# Motor_Phase.net
KiCad netlist of a schematic drawn in Altium Designer
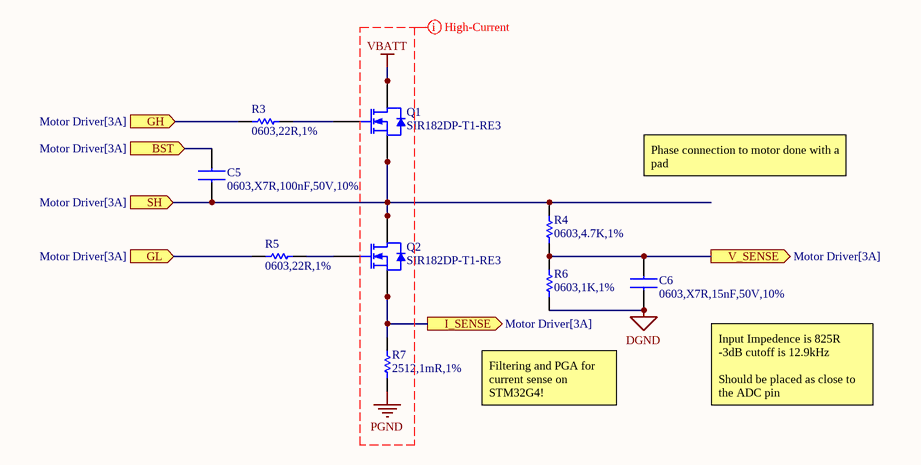
[diagram p0: Motor Phase.SchDoc]

(export (version "E")
  (design (tool "Eeschema 10.0.6"))
  (components
    (comp (ref "C5")
      (value "0603,X7R,100nF,50V,10%")
      (footprint "CAPC1608X90N")
      (description "50V 100nF X7R ±10% 0603 Multilayer Ceramic Capacitors MLCC - SMD/SMT ROHS")
      (fields
        (field (name "MANUFACTURER_PART_NUMBER") "CC0603KRX7R9BB104")
        (field (name "MOUSER PART NUMBER") "603-CC603KRX7R9BB104")
      )
      (libsource (lib "ESC") (part "CC0603KRX7R9BB104"))
    )
    (comp (ref "C6")
      (value "0603,X7R,15nF,50V,10%")
      (footprint "CAPC1608X90N")
      (description "50V 15nF X7R ±10% 0603 Multilayer Ceramic Capacitors MLCC - SMD/SMT ROHS")
      (fields
        (field (name "MANUFACTURER_PART_NUMBER") "CC0603KRX7R9BB153")
        (field (name "MOUSER PART NUMBER") "603-CC603KRX7R9BB104")
      )
      (libsource (lib "ESC") (part "CC0603KRX7R9BB153"))
    )
    (comp (ref "Q1")
      (value "SIR182DP-T1-RE3")
      (footprint "POWERPAK-SO-8_L5.9-W4.9-P1.27-LS6.2-BL")
      (description "60V 117A 2.8mΩ@10V,15A 2V 1 N-Channel PowerPAKSO-8 MOSFETs ROHS")
      (fields (field (name "LCSC PART #") "C467943"))
      (libsource (lib "ESC") (part "SIR182DP-T1-RE3"))
    )
    (comp (ref "Q2")
      (value "SIR182DP-T1-RE3")
      (footprint "POWERPAK-SO-8_L5.9-W4.9-P1.27-LS6.2-BL")
      (description "60V 117A 2.8mΩ@10V,15A 2V 1 N-Channel PowerPAKSO-8 MOSFETs ROHS")
      (fields (field (name "LCSC PART #") "C467943"))
      (libsource (lib "ESC") (part "SIR182DP-T1-RE3"))
    )
    (comp (ref "R3")
      (value "0603,22R,1%")
      (footprint "RESC1608X55N")
      (description "100mW Thick Film Resistor 75V ±100ppm/℃ ±1% 22Ω 0603 Chip Resistor - Surface Mount ROHS")
      (fields
        (field (name "MANUFACTURER_PART_NUMBER") "RC0603FR-0722RL")
        (field (name "MOUSER PART NUMBER") "603-RC0603FR-0722RL")
      )
      (libsource (lib "ESC") (part "RC0603FR-0722RL"))
    )
    (comp (ref "R4")
      (value "0603,4.7K,1%")
      (footprint "RESC1608X55N")
      (description "100mW Thick Film Resistor 75V ±100ppm/℃ ±1% 4.7kΩ 0603 Chip Resistor - Surface Mount ROHS")
      (fields
        (field (name "MANUFACTURER_PART_NUMBER") "RC0603FR-074K7L")
        (field (name "LCSC PART #") "C99782")
      )
      (libsource (lib "ESC") (part "RC0603FR-074K7L"))
    )
    (comp (ref "R5")
      (value "0603,22R,1%")
      (footprint "RESC1608X55N")
      (description "100mW Thick Film Resistor 75V ±100ppm/℃ ±1% 22Ω 0603 Chip Resistor - Surface Mount ROHS")
      (fields
        (field (name "MANUFACTURER_PART_NUMBER") "RC0603FR-0722RL")
        (field (name "MOUSER PART NUMBER") "603-RC0603FR-0722RL")
      )
      (libsource (lib "ESC") (part "RC0603FR-0722RL"))
    )
    (comp (ref "R6")
      (value "0603,1K,1%")
      (footprint "RESC1608X55N")
      (description "100mW Thick Film Resistor 75V ±100ppm/℃ ±1% 1kΩ 0603 Chip Resistor - Surface Mount ROHS")
      (fields
        (field (name "MANUFACTURER_PART_NUMBER") "RC0603FR-071KL")
        (field (name "LCSC PART #") "C22548")
      )
      (libsource (lib "ESC") (part "RC0603FR-071KL"))
    )
    (comp (ref "R7")
      (value "2512,1mR,1%")
      (footprint "RES-SMD_L6.4-W3.2_RLP25")
      (fields (field (name "LCSC PART #") "C723380"))
      (libsource (lib "ESC") (part "PA2512FKF7T0R001E"))
    )
  )
  (nets
    (net (code "1") (name "/BST") (class "Default")
      (node (ref "C5") (pin "2") (pinfunction "2_2") (pintype "passive"))
    )
    (net (code "2") (name "/GH") (class "Default")
      (node (ref "R3") (pin "1") (pinfunction "1_1") (pintype "passive"))
    )
    (net (code "3") (name "/GL") (class "Default")
      (node (ref "R5") (pin "1") (pinfunction "1_1") (pintype "passive"))
    )
    (net (code "4") (name "/I_SENSE") (class "Default")
      (node (ref "Q2") (pin "1") (pinfunction "S_1") (pintype "passive"))
      (node (ref "Q2") (pin "2") (pinfunction "S_2") (pintype "passive"))
      (node (ref "Q2") (pin "3") (pinfunction "S_3") (pintype "passive"))
      (node (ref "R7") (pin "2") (pinfunction "2_2") (pintype "passive"))
    )
    (net (code "5") (name "/SH") (class "Default")
      (node (ref "C5") (pin "1") (pinfunction "1_1") (pintype "passive"))
      (node (ref "Q1") (pin "1") (pinfunction "S_1") (pintype "passive"))
      (node (ref "Q1") (pin "2") (pinfunction "S_2") (pintype "passive"))
      (node (ref "Q1") (pin "3") (pinfunction "S_3") (pintype "passive"))
      (node (ref "Q2") (pin "5") (pinfunction "D_5") (pintype "passive"))
      (node (ref "Q2") (pin "6") (pinfunction "D_6") (pintype "passive"))
      (node (ref "Q2") (pin "7") (pinfunction "D_7") (pintype "passive"))
      (node (ref "Q2") (pin "8") (pinfunction "D_8") (pintype "passive"))
      (node (ref "R4") (pin "2") (pinfunction "2_2") (pintype "passive"))
    )
    (net (code "6") (name "/V_SENSE") (class "Default")
      (node (ref "C6") (pin "2") (pinfunction "2_2") (pintype "passive"))
      (node (ref "R4") (pin "1") (pinfunction "1_1") (pintype "passive"))
      (node (ref "R6") (pin "2") (pinfunction "2_2") (pintype "passive"))
    )
    (net (code "7") (name "DGND") (class "Default")
      (node (ref "C6") (pin "1") (pinfunction "1_1") (pintype "passive"))
      (node (ref "R6") (pin "1") (pinfunction "1_1") (pintype "passive"))
    )
    (net (code "8") (name "Net-(Q1-G)") (class "Default")
      (node (ref "Q1") (pin "4") (pinfunction "G_4") (pintype "passive"))
      (node (ref "R3") (pin "2") (pinfunction "2_2") (pintype "passive"))
    )
    (net (code "9") (name "Net-(Q2-G)") (class "Default")
      (node (ref "Q2") (pin "4") (pinfunction "G_4") (pintype "passive"))
      (node (ref "R5") (pin "2") (pinfunction "2_2") (pintype "passive"))
    )
    (net (code "10") (name "PGND") (class "Default")
      (node (ref "R7") (pin "1") (pinfunction "1_1") (pintype "passive"))
    )
    (net (code "11") (name "VBATT") (class "Default")
      (node (ref "Q1") (pin "5") (pinfunction "D_5") (pintype "passive"))
      (node (ref "Q1") (pin "6") (pinfunction "D_6") (pintype "passive"))
      (node (ref "Q1") (pin "7") (pinfunction "D_7") (pintype "passive"))
      (node (ref "Q1") (pin "8") (pinfunction "D_8") (pintype "passive"))
    )
  )
)
